# ProPrj_FC_1_2025-02-16.net
KiCad netlist of a schematic drawn in EasyEDA Pro
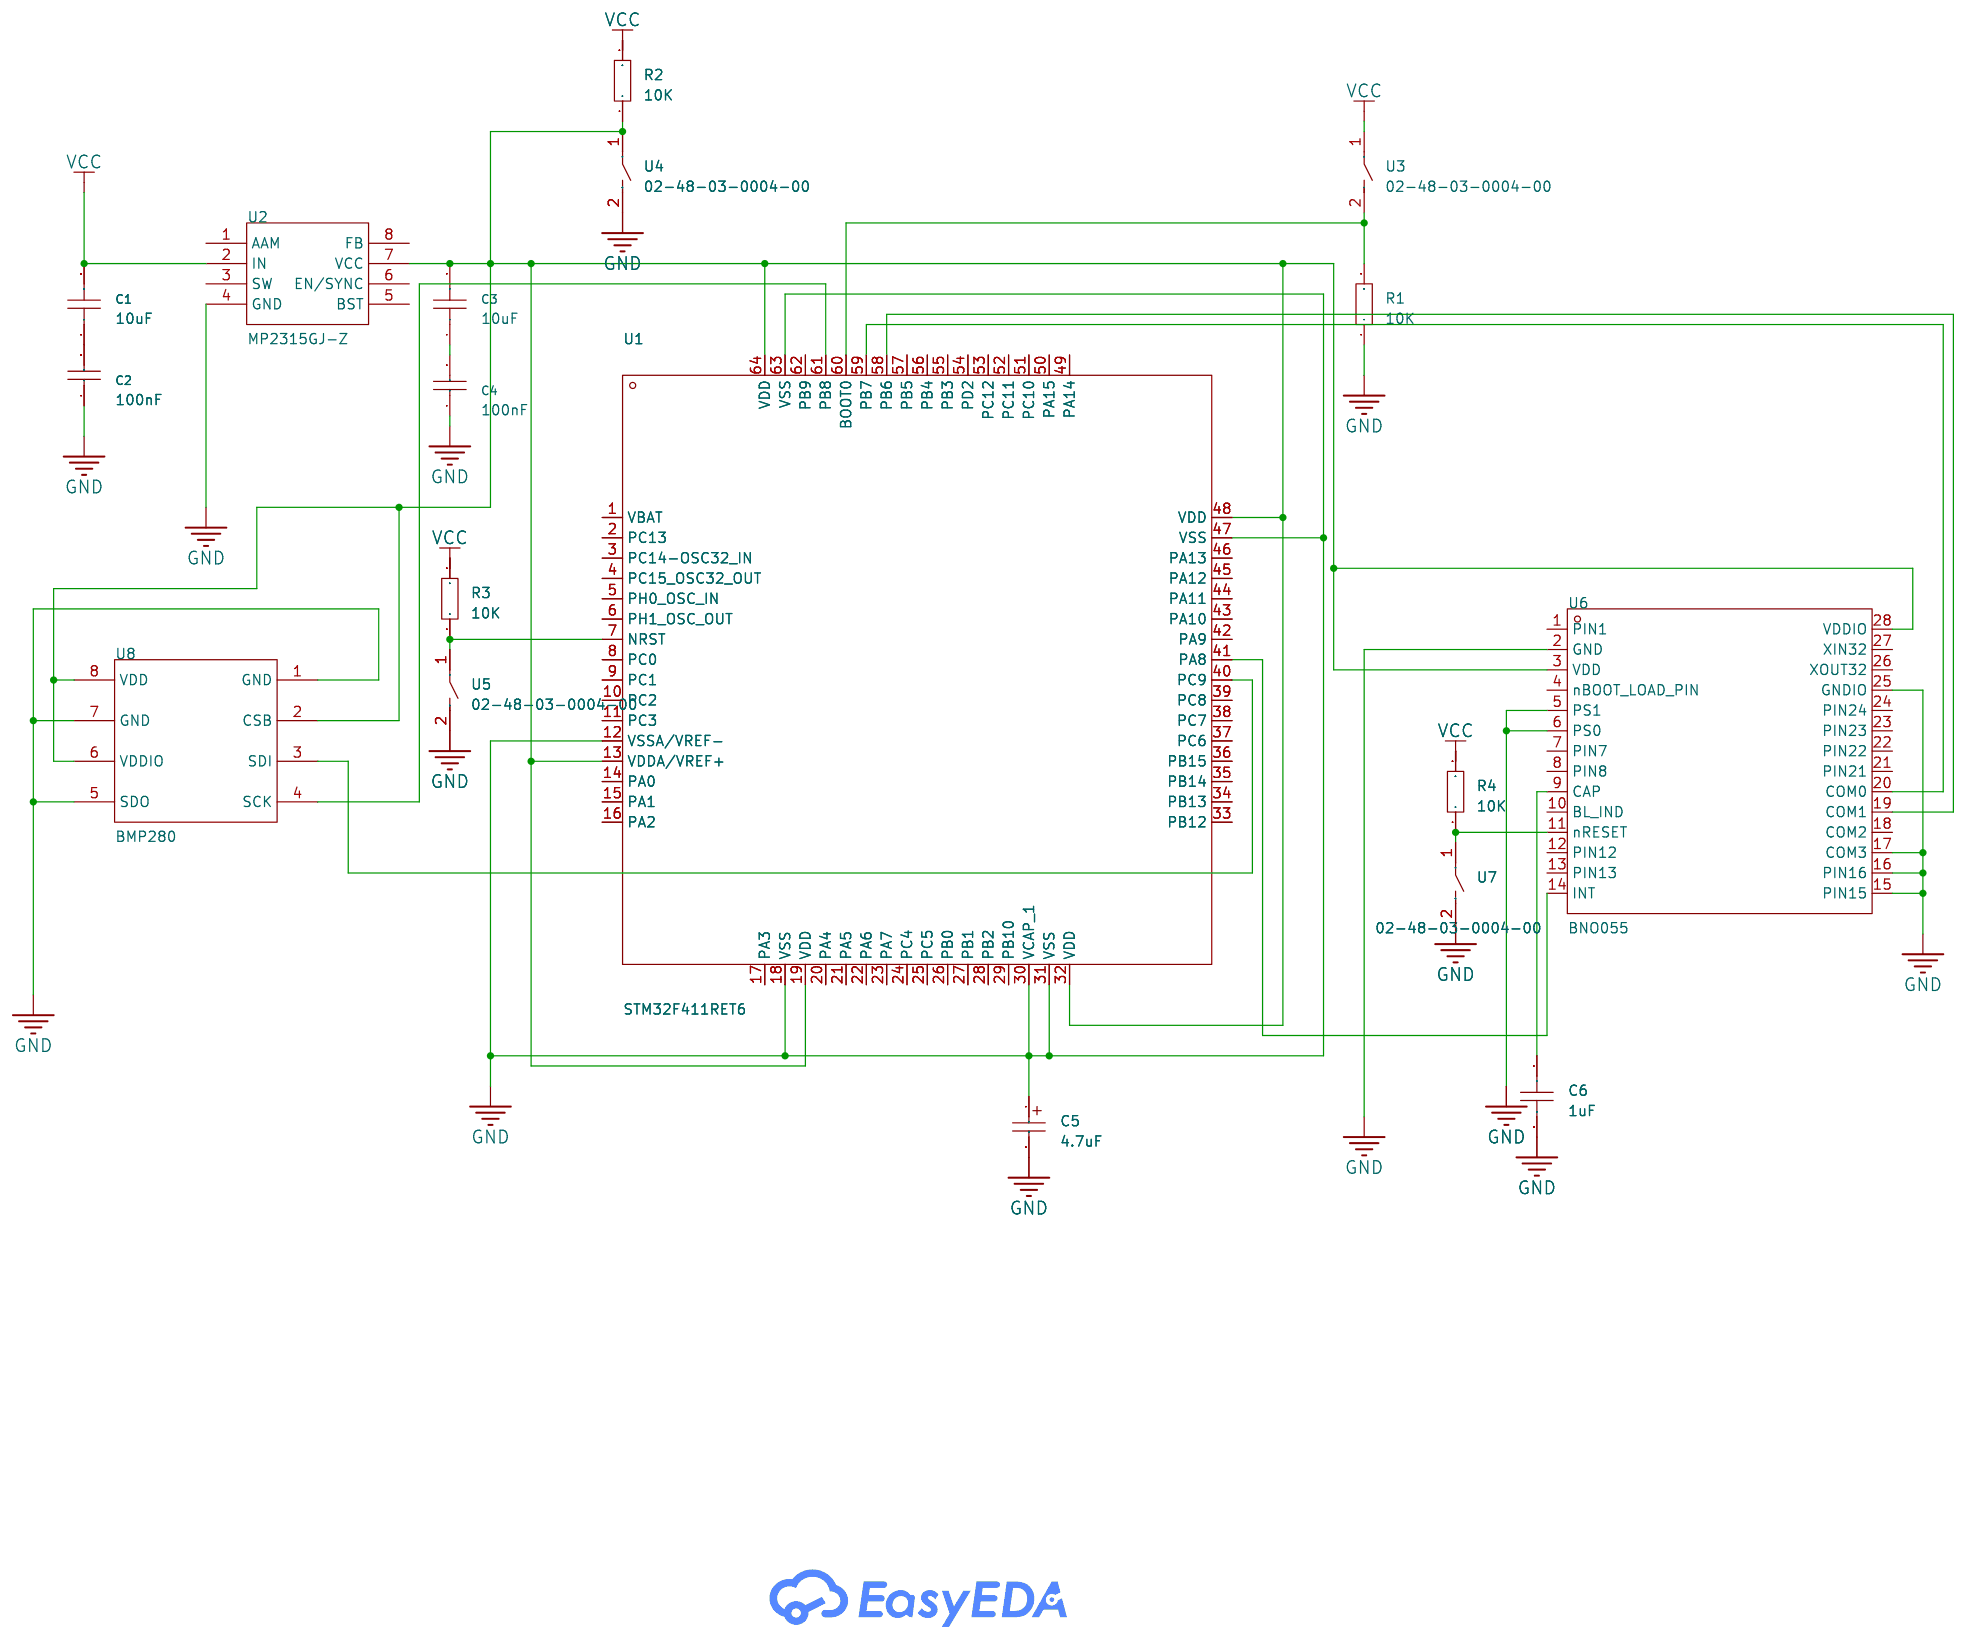
[diagram p0: schematic sheet]

(export (version "E")
  (design (tool "Eeschema 10.0.6"))
  (components
    (comp (ref "C1")
      (value "10uF")
      (footprint "easyedapro:C0603")
      (fields
        (field (name "Manufacturer Part") "CL10A106MA8NRNC")
        (field (name "Manufacturer") "SAMSUNG(三星)")
      )
      (libsource (lib "easyedapro") (part "CL10A106MA8NRNC"))
    )
    (comp (ref "C2")
      (value "100nF")
      (footprint "easyedapro:C1206")
      (fields
        (field (name "Manufacturer Part") "CL31B104KBCNNNC")
        (field (name "Manufacturer") "SAMSUNG(三星)")
      )
      (libsource (lib "easyedapro") (part "CL31B104KBCNNNC"))
    )
    (comp (ref "C3")
      (value "10uF")
      (footprint "easyedapro:C0603")
      (fields
        (field (name "Manufacturer Part") "CL10A106MA8NRNC")
        (field (name "Manufacturer") "SAMSUNG(三星)")
      )
      (libsource (lib "easyedapro") (part "CL10A106MA8NRNC"))
    )
    (comp (ref "C4")
      (value "100nF")
      (footprint "easyedapro:C1206")
      (fields
        (field (name "Manufacturer Part") "CL31B104KBCNNNC")
        (field (name "Manufacturer") "SAMSUNG(三星)")
      )
      (libsource (lib "easyedapro") (part "CL31B104KBCNNNC"))
    )
    (comp (ref "C5")
      (value "4.7uF")
      (footprint "easyedapro:CAP-SMD_L3.5-W2.8")
      (fields
        (field (name "Manufacturer Part") "CA45B-B-35V-4.7UF-K")
        (field (name "Manufacturer") "CEC(振华新云)")
      )
      (libsource (lib "easyedapro") (part "CA45B-B-35V-4.7UF-K"))
    )
    (comp (ref "C6") (value "1uF") (footprint "easyedapro:C0603") (libsource (lib "easyedapro") (part "CAP")))
    (comp (ref "R1") (value "10K") (footprint "easyedapro:R0603") (libsource (lib "easyedapro") (part "Res")))
    (comp (ref "R2") (value "10K") (footprint "easyedapro:R0603") (libsource (lib "easyedapro") (part "Res")))
    (comp (ref "R3") (value "10K") (footprint "easyedapro:R0603") (libsource (lib "easyedapro") (part "Res")))
    (comp (ref "R4") (value "10K") (footprint "easyedapro:R0603") (libsource (lib "easyedapro") (part "Res")))
    (comp (ref "U1")
      (value "STM32F411RET6")
      (footprint "easyedapro:LQFP-64_L10.0-W10.0-P0.50-LS12.0-BL")
      (fields (field (name "Manufacturer") "ST(意法半导体)"))
      (libsource (lib "easyedapro") (part "STM32F411RET6"))
    )
    (comp (ref "U2")
      (value "MP2315GJ-Z")
      (footprint "easyedapro:TSOT-23-8_L2.9-W1.6-P0.65-LS2.8-BR")
      (fields (field (name "Manufacturer") "MPS(芯源)"))
      (libsource (lib "easyedapro") (part "MP2315GJ-Z"))
    )
    (comp (ref "U3")
      (value "02-48-03-0004-00")
      (footprint "easyedapro:KEY-SMD_L6.0-W3.5-LS8.0-1")
      (libsource (lib "easyedapro") (part "02-48-03-0004-00"))
    )
    (comp (ref "U4")
      (value "02-48-03-0004-00")
      (footprint "easyedapro:KEY-SMD_L6.0-W3.5-LS8.0-1")
      (libsource (lib "easyedapro") (part "02-48-03-0004-00"))
    )
    (comp (ref "U5")
      (value "02-48-03-0004-00")
      (footprint "easyedapro:KEY-SMD_L6.0-W3.5-LS8.0-1")
      (libsource (lib "easyedapro") (part "02-48-03-0004-00"))
    )
    (comp (ref "U6")
      (value "BNO055")
      (footprint "easyedapro:LGA-28_L5.2-W3.8-P0.50-BL")
      (fields (field (name "Manufacturer") "Bosch(博世)"))
      (libsource (lib "easyedapro") (part "BNO055"))
    )
    (comp (ref "U7")
      (value "02-48-03-0004-00")
      (footprint "easyedapro:KEY-SMD_L6.0-W3.5-LS8.0-1")
      (libsource (lib "easyedapro") (part "02-48-03-0004-00"))
    )
    (comp (ref "U8")
      (value "BMP280")
      (footprint "easyedapro:LGA-8_L2.5-W2.0-P0.65_AMP6127")
      (fields (field (name "Manufacturer") "Bosch(博世)"))
      (libsource (lib "easyedapro") (part "BMP280"))
    )
  )
  (nets
    (net (code "1") (name "GND") (class "Default")
      (node (ref "C2") (pin "1") (pinfunction "1_1") (pintype "input"))
      (node (ref "C4") (pin "1") (pinfunction "1_1") (pintype "input"))
      (node (ref "C5") (pin "1") (pinfunction "1_1") (pintype "input"))
      (node (ref "C5") (pin "2") (pinfunction "2_2") (pintype "input"))
      (node (ref "C6") (pin "2") (pinfunction "2_2") (pintype "input"))
      (node (ref "R1") (pin "1") (pinfunction "1_1") (pintype "input"))
      (node (ref "U1") (pin "12") (pinfunction "VSSA/VREF-_12") (pintype "unspecified"))
      (node (ref "U1") (pin "18") (pinfunction "VSS_18") (pintype "unspecified"))
      (node (ref "U1") (pin "30") (pinfunction "VCAP_1_30") (pintype "unspecified"))
      (node (ref "U1") (pin "31") (pinfunction "VSS_31") (pintype "unspecified"))
      (node (ref "U1") (pin "47") (pinfunction "VSS_47") (pintype "unspecified"))
      (node (ref "U1") (pin "63") (pinfunction "VSS_63") (pintype "unspecified"))
      (node (ref "U2") (pin "4") (pinfunction "GND_4") (pintype "unspecified"))
      (node (ref "U4") (pin "2") (pinfunction "2_2") (pintype "unspecified"))
      (node (ref "U5") (pin "2") (pinfunction "2_2") (pintype "unspecified"))
      (node (ref "U6") (pin "15") (pinfunction "PIN15_15") (pintype "unspecified"))
      (node (ref "U6") (pin "16") (pinfunction "PIN16_16") (pintype "unspecified"))
      (node (ref "U6") (pin "17") (pinfunction "COM3_17") (pintype "unspecified"))
      (node (ref "U6") (pin "2") (pinfunction "GND_2") (pintype "unspecified"))
      (node (ref "U6") (pin "25") (pinfunction "GNDIO_25") (pintype "unspecified"))
      (node (ref "U6") (pin "5") (pinfunction "PS1_5") (pintype "unspecified"))
      (node (ref "U6") (pin "6") (pinfunction "PS0_6") (pintype "unspecified"))
      (node (ref "U7") (pin "2") (pinfunction "2_2") (pintype "unspecified"))
      (node (ref "U8") (pin "1") (pinfunction "GND_1") (pintype "unspecified"))
      (node (ref "U8") (pin "5") (pinfunction "SDO_5") (pintype "unspecified"))
      (node (ref "U8") (pin "7") (pinfunction "GND_7") (pintype "unspecified"))
    )
    (net (code "2") (name "Net-(C1-Pad1)") (class "Default")
      (node (ref "C1") (pin "1") (pinfunction "1_1") (pintype "input"))
      (node (ref "C2") (pin "2") (pinfunction "2_2") (pintype "input"))
    )
    (net (code "3") (name "Net-(C3-Pad1)") (class "Default")
      (node (ref "C3") (pin "1") (pinfunction "1_1") (pintype "input"))
      (node (ref "C4") (pin "2") (pinfunction "2_2") (pintype "input"))
    )
    (net (code "4") (name "Net-(U1-BOOT0)") (class "Default")
      (node (ref "R1") (pin "2") (pinfunction "2_2") (pintype "input"))
      (node (ref "U1") (pin "60") (pinfunction "BOOT0_60") (pintype "unspecified"))
      (node (ref "U3") (pin "2") (pinfunction "2_2") (pintype "unspecified"))
    )
    (net (code "5") (name "Net-(U1-NRST)") (class "Default")
      (node (ref "R3") (pin "1") (pinfunction "1_1") (pintype "input"))
      (node (ref "U1") (pin "7") (pinfunction "NRST_7") (pintype "unspecified"))
      (node (ref "U5") (pin "1") (pinfunction "1_1") (pintype "unspecified"))
    )
    (net (code "6") (name "Net-(U1-PA8)") (class "Default")
      (node (ref "U1") (pin "41") (pinfunction "PA8_41") (pintype "unspecified"))
      (node (ref "U6") (pin "14") (pinfunction "INT_14") (pintype "unspecified"))
    )
    (net (code "7") (name "Net-(U1-PB6)") (class "Default")
      (node (ref "U1") (pin "58") (pinfunction "PB6_58") (pintype "unspecified"))
      (node (ref "U6") (pin "19") (pinfunction "COM1_19") (pintype "unspecified"))
    )
    (net (code "8") (name "Net-(U1-PB7)") (class "Default")
      (node (ref "U1") (pin "59") (pinfunction "PB7_59") (pintype "unspecified"))
      (node (ref "U6") (pin "20") (pinfunction "COM0_20") (pintype "unspecified"))
    )
    (net (code "9") (name "Net-(U1-PB8)") (class "Default")
      (node (ref "U1") (pin "61") (pinfunction "PB8_61") (pintype "unspecified"))
      (node (ref "U8") (pin "4") (pinfunction "SCK_4") (pintype "unspecified"))
    )
    (net (code "10") (name "Net-(U1-PC9)") (class "Default")
      (node (ref "U1") (pin "40") (pinfunction "PC9_40") (pintype "unspecified"))
      (node (ref "U8") (pin "3") (pinfunction "SDI_3") (pintype "unspecified"))
    )
    (net (code "11") (name "Net-(U1-VDDA{slash}VREF+)") (class "Default")
      (node (ref "C3") (pin "2") (pinfunction "2_2") (pintype "input"))
      (node (ref "R2") (pin "1") (pinfunction "1_1") (pintype "input"))
      (node (ref "U1") (pin "13") (pinfunction "VDDA/VREF+_13") (pintype "unspecified"))
      (node (ref "U1") (pin "19") (pinfunction "VDD_19") (pintype "unspecified"))
      (node (ref "U1") (pin "32") (pinfunction "VDD_32") (pintype "unspecified"))
      (node (ref "U1") (pin "48") (pinfunction "VDD_48") (pintype "unspecified"))
      (node (ref "U1") (pin "64") (pinfunction "VDD_64") (pintype "unspecified"))
      (node (ref "U2") (pin "7") (pinfunction "VCC_7") (pintype "unspecified"))
      (node (ref "U4") (pin "1") (pinfunction "1_1") (pintype "unspecified"))
      (node (ref "U6") (pin "28") (pinfunction "VDDIO_28") (pintype "unspecified"))
      (node (ref "U6") (pin "3") (pinfunction "VDD_3") (pintype "unspecified"))
      (node (ref "U8") (pin "2") (pinfunction "CSB_2") (pintype "unspecified"))
      (node (ref "U8") (pin "6") (pinfunction "VDDIO_6") (pintype "unspecified"))
      (node (ref "U8") (pin "8") (pinfunction "VDD_8") (pintype "unspecified"))
    )
    (net (code "12") (name "Net-(U6-CAP)") (class "Default")
      (node (ref "C6") (pin "1") (pinfunction "1_1") (pintype "input"))
      (node (ref "U6") (pin "9") (pinfunction "CAP_9") (pintype "unspecified"))
    )
    (net (code "13") (name "Net-(U6-nRESET)") (class "Default")
      (node (ref "R4") (pin "1") (pinfunction "1_1") (pintype "input"))
      (node (ref "U6") (pin "11") (pinfunction "nRESET_11") (pintype "unspecified"))
      (node (ref "U7") (pin "1") (pinfunction "1_1") (pintype "unspecified"))
    )
    (net (code "14") (name "VCC") (class "Default")
      (node (ref "C1") (pin "2") (pinfunction "2_2") (pintype "input"))
      (node (ref "R2") (pin "2") (pinfunction "2_2") (pintype "input"))
      (node (ref "R3") (pin "2") (pinfunction "2_2") (pintype "input"))
      (node (ref "R4") (pin "2") (pinfunction "2_2") (pintype "input"))
      (node (ref "U2") (pin "2") (pinfunction "IN_2") (pintype "unspecified"))
      (node (ref "U3") (pin "1") (pinfunction "1_1") (pintype "unspecified"))
    )
    (net (code "15") (name "unconnected-(U1-PA0-Pad14)") (class "Default")
      (node (ref "U1") (pin "14") (pinfunction "PA0_14") (pintype "unspecified"))
    )
    (net (code "16") (name "unconnected-(U1-PA1-Pad15)") (class "Default")
      (node (ref "U1") (pin "15") (pinfunction "PA1_15") (pintype "unspecified"))
    )
    (net (code "17") (name "unconnected-(U1-PA2-Pad16)") (class "Default")
      (node (ref "U1") (pin "16") (pinfunction "PA2_16") (pintype "unspecified"))
    )
    (net (code "18") (name "unconnected-(U1-PA3-Pad17)") (class "Default")
      (node (ref "U1") (pin "17") (pinfunction "PA3_17") (pintype "unspecified"))
    )
    (net (code "19") (name "unconnected-(U1-PA4-Pad20)") (class "Default")
      (node (ref "U1") (pin "20") (pinfunction "PA4_20") (pintype "unspecified"))
    )
    (net (code "20") (name "unconnected-(U1-PA5-Pad21)") (class "Default")
      (node (ref "U1") (pin "21") (pinfunction "PA5_21") (pintype "unspecified"))
    )
    (net (code "21") (name "unconnected-(U1-PA6-Pad22)") (class "Default")
      (node (ref "U1") (pin "22") (pinfunction "PA6_22") (pintype "unspecified"))
    )
    (net (code "22") (name "unconnected-(U1-PA7-Pad23)") (class "Default")
      (node (ref "U1") (pin "23") (pinfunction "PA7_23") (pintype "unspecified"))
    )
    (net (code "23") (name "unconnected-(U1-PA9-Pad42)") (class "Default")
      (node (ref "U1") (pin "42") (pinfunction "PA9_42") (pintype "unspecified"))
    )
    (net (code "24") (name "unconnected-(U1-PA10-Pad43)") (class "Default")
      (node (ref "U1") (pin "43") (pinfunction "PA10_43") (pintype "unspecified"))
    )
    (net (code "25") (name "unconnected-(U1-PA11-Pad44)") (class "Default")
      (node (ref "U1") (pin "44") (pinfunction "PA11_44") (pintype "unspecified"))
    )
    (net (code "26") (name "unconnected-(U1-PA12-Pad45)") (class "Default")
      (node (ref "U1") (pin "45") (pinfunction "PA12_45") (pintype "unspecified"))
    )
    (net (code "27") (name "unconnected-(U1-PA13-Pad46)") (class "Default")
      (node (ref "U1") (pin "46") (pinfunction "PA13_46") (pintype "unspecified"))
    )
    (net (code "28") (name "unconnected-(U1-PA14-Pad49)") (class "Default")
      (node (ref "U1") (pin "49") (pinfunction "PA14_49") (pintype "unspecified"))
    )
    (net (code "29") (name "unconnected-(U1-PA15-Pad50)") (class "Default")
      (node (ref "U1") (pin "50") (pinfunction "PA15_50") (pintype "unspecified"))
    )
    (net (code "30") (name "unconnected-(U1-PB0-Pad26)") (class "Default")
      (node (ref "U1") (pin "26") (pinfunction "PB0_26") (pintype "unspecified"))
    )
    (net (code "31") (name "unconnected-(U1-PB1-Pad27)") (class "Default")
      (node (ref "U1") (pin "27") (pinfunction "PB1_27") (pintype "unspecified"))
    )
    (net (code "32") (name "unconnected-(U1-PB2-Pad28)") (class "Default")
      (node (ref "U1") (pin "28") (pinfunction "PB2_28") (pintype "unspecified"))
    )
    (net (code "33") (name "unconnected-(U1-PB3-Pad55)") (class "Default")
      (node (ref "U1") (pin "55") (pinfunction "PB3_55") (pintype "unspecified"))
    )
    (net (code "34") (name "unconnected-(U1-PB4-Pad56)") (class "Default")
      (node (ref "U1") (pin "56") (pinfunction "PB4_56") (pintype "unspecified"))
    )
    (net (code "35") (name "unconnected-(U1-PB5-Pad57)") (class "Default")
      (node (ref "U1") (pin "57") (pinfunction "PB5_57") (pintype "unspecified"))
    )
    (net (code "36") (name "unconnected-(U1-PB9-Pad62)") (class "Default")
      (node (ref "U1") (pin "62") (pinfunction "PB9_62") (pintype "unspecified"))
    )
    (net (code "37") (name "unconnected-(U1-PB10-Pad29)") (class "Default")
      (node (ref "U1") (pin "29") (pinfunction "PB10_29") (pintype "unspecified"))
    )
    (net (code "38") (name "unconnected-(U1-PB12-Pad33)") (class "Default")
      (node (ref "U1") (pin "33") (pinfunction "PB12_33") (pintype "unspecified"))
    )
    (net (code "39") (name "unconnected-(U1-PB13-Pad34)") (class "Default")
      (node (ref "U1") (pin "34") (pinfunction "PB13_34") (pintype "unspecified"))
    )
    (net (code "40") (name "unconnected-(U1-PB14-Pad35)") (class "Default")
      (node (ref "U1") (pin "35") (pinfunction "PB14_35") (pintype "unspecified"))
    )
    (net (code "41") (name "unconnected-(U1-PB15-Pad36)") (class "Default")
      (node (ref "U1") (pin "36") (pinfunction "PB15_36") (pintype "unspecified"))
    )
    (net (code "42") (name "unconnected-(U1-PC0-Pad8)") (class "Default")
      (node (ref "U1") (pin "8") (pinfunction "PC0_8") (pintype "unspecified"))
    )
    (net (code "43") (name "unconnected-(U1-PC1-Pad9)") (class "Default")
      (node (ref "U1") (pin "9") (pinfunction "PC1_9") (pintype "unspecified"))
    )
    (net (code "44") (name "unconnected-(U1-PC2-Pad10)") (class "Default")
      (node (ref "U1") (pin "10") (pinfunction "PC2_10") (pintype "unspecified"))
    )
    (net (code "45") (name "unconnected-(U1-PC3-Pad11)") (class "Default")
      (node (ref "U1") (pin "11") (pinfunction "PC3_11") (pintype "unspecified"))
    )
    (net (code "46") (name "unconnected-(U1-PC4-Pad24)") (class "Default")
      (node (ref "U1") (pin "24") (pinfunction "PC4_24") (pintype "unspecified"))
    )
    (net (code "47") (name "unconnected-(U1-PC5-Pad25)") (class "Default")
      (node (ref "U1") (pin "25") (pinfunction "PC5_25") (pintype "unspecified"))
    )
    (net (code "48") (name "unconnected-(U1-PC6-Pad37)") (class "Default")
      (node (ref "U1") (pin "37") (pinfunction "PC6_37") (pintype "unspecified"))
    )
    (net (code "49") (name "unconnected-(U1-PC7-Pad38)") (class "Default")
      (node (ref "U1") (pin "38") (pinfunction "PC7_38") (pintype "unspecified"))
    )
    (net (code "50") (name "unconnected-(U1-PC8-Pad39)") (class "Default")
      (node (ref "U1") (pin "39") (pinfunction "PC8_39") (pintype "unspecified"))
    )
    (net (code "51") (name "unconnected-(U1-PC10-Pad51)") (class "Default")
      (node (ref "U1") (pin "51") (pinfunction "PC10_51") (pintype "unspecified"))
    )
    (net (code "52") (name "unconnected-(U1-PC11-Pad52)") (class "Default")
      (node (ref "U1") (pin "52") (pinfunction "PC11_52") (pintype "unspecified"))
    )
    (net (code "53") (name "unconnected-(U1-PC12-Pad53)") (class "Default")
      (node (ref "U1") (pin "53") (pinfunction "PC12_53") (pintype "unspecified"))
    )
    (net (code "54") (name "unconnected-(U1-PC13-Pad2)") (class "Default")
      (node (ref "U1") (pin "2") (pinfunction "PC13_2") (pintype "unspecified"))
    )
    (net (code "55") (name "unconnected-(U1-PC14-OSC32_IN-Pad3)") (class "Default")
      (node (ref "U1") (pin "3") (pinfunction "PC14-OSC32_IN_3") (pintype "unspecified"))
    )
    (net (code "56") (name "unconnected-(U1-PC15_OSC32_OUT-Pad4)") (class "Default")
      (node (ref "U1") (pin "4") (pinfunction "PC15_OSC32_OUT_4") (pintype "unspecified"))
    )
    (net (code "57") (name "unconnected-(U1-PD2-Pad54)") (class "Default")
      (node (ref "U1") (pin "54") (pinfunction "PD2_54") (pintype "unspecified"))
    )
    (net (code "58") (name "unconnected-(U1-PH0_OSC_IN-Pad5)") (class "Default")
      (node (ref "U1") (pin "5") (pinfunction "PH0_OSC_IN_5") (pintype "unspecified"))
    )
    (net (code "59") (name "unconnected-(U1-PH1_OSC_OUT-Pad6)") (class "Default")
      (node (ref "U1") (pin "6") (pinfunction "PH1_OSC_OUT_6") (pintype "unspecified"))
    )
    (net (code "60") (name "unconnected-(U1-VBAT-Pad1)") (class "Default")
      (node (ref "U1") (pin "1") (pinfunction "VBAT_1") (pintype "unspecified"))
    )
    (net (code "61") (name "unconnected-(U2-AAM-Pad1)") (class "Default")
      (node (ref "U2") (pin "1") (pinfunction "AAM_1") (pintype "unspecified"))
    )
    (net (code "62") (name "unconnected-(U2-BST-Pad5)") (class "Default")
      (node (ref "U2") (pin "5") (pinfunction "BST_5") (pintype "unspecified"))
    )
    (net (code "63") (name "unconnected-(U2-EN{slash}SYNC-Pad6)") (class "Default")
      (node (ref "U2") (pin "6") (pinfunction "EN/SYNC_6") (pintype "unspecified"))
    )
    (net (code "64") (name "unconnected-(U2-FB-Pad8)") (class "Default")
      (node (ref "U2") (pin "8") (pinfunction "FB_8") (pintype "unspecified"))
    )
    (net (code "65") (name "unconnected-(U2-SW-Pad3)") (class "Default")
      (node (ref "U2") (pin "3") (pinfunction "SW_3") (pintype "unspecified"))
    )
    (net (code "66") (name "unconnected-(U6-BL_IND-Pad10)") (class "Default")
      (node (ref "U6") (pin "10") (pinfunction "BL_IND_10") (pintype "unspecified"))
    )
    (net (code "67") (name "unconnected-(U6-COM2-Pad18)") (class "Default")
      (node (ref "U6") (pin "18") (pinfunction "COM2_18") (pintype "unspecified"))
    )
    (net (code "68") (name "unconnected-(U6-PIN1-Pad1)") (class "Default")
      (node (ref "U6") (pin "1") (pinfunction "PIN1_1") (pintype "unspecified"))
    )
    (net (code "69") (name "unconnected-(U6-PIN7-Pad7)") (class "Default")
      (node (ref "U6") (pin "7") (pinfunction "PIN7_7") (pintype "unspecified"))
    )
    (net (code "70") (name "unconnected-(U6-PIN8-Pad8)") (class "Default")
      (node (ref "U6") (pin "8") (pinfunction "PIN8_8") (pintype "unspecified"))
    )
    (net (code "71") (name "unconnected-(U6-PIN12-Pad12)") (class "Default")
      (node (ref "U6") (pin "12") (pinfunction "PIN12_12") (pintype "unspecified"))
    )
    (net (code "72") (name "unconnected-(U6-PIN13-Pad13)") (class "Default")
      (node (ref "U6") (pin "13") (pinfunction "PIN13_13") (pintype "unspecified"))
    )
    (net (code "73") (name "unconnected-(U6-PIN21-Pad21)") (class "Default")
      (node (ref "U6") (pin "21") (pinfunction "PIN21_21") (pintype "unspecified"))
    )
    (net (code "74") (name "unconnected-(U6-PIN22-Pad22)") (class "Default")
      (node (ref "U6") (pin "22") (pinfunction "PIN22_22") (pintype "unspecified"))
    )
    (net (code "75") (name "unconnected-(U6-PIN23-Pad23)") (class "Default")
      (node (ref "U6") (pin "23") (pinfunction "PIN23_23") (pintype "unspecified"))
    )
    (net (code "76") (name "unconnected-(U6-PIN24-Pad24)") (class "Default")
      (node (ref "U6") (pin "24") (pinfunction "PIN24_24") (pintype "unspecified"))
    )
    (net (code "77") (name "unconnected-(U6-XIN32-Pad27)") (class "Default")
      (node (ref "U6") (pin "27") (pinfunction "XIN32_27") (pintype "unspecified"))
    )
    (net (code "78") (name "unconnected-(U6-XOUT32-Pad26)") (class "Default")
      (node (ref "U6") (pin "26") (pinfunction "XOUT32_26") (pintype "unspecified"))
    )
    (net (code "79") (name "unconnected-(U6-nBOOT_LOAD_PIN-Pad4)") (class "Default")
      (node (ref "U6") (pin "4") (pinfunction "nBOOT_LOAD_PIN_4") (pintype "unspecified"))
    )
  )
)
